# Power.net
KiCad netlist of a schematic drawn in Altium Designer
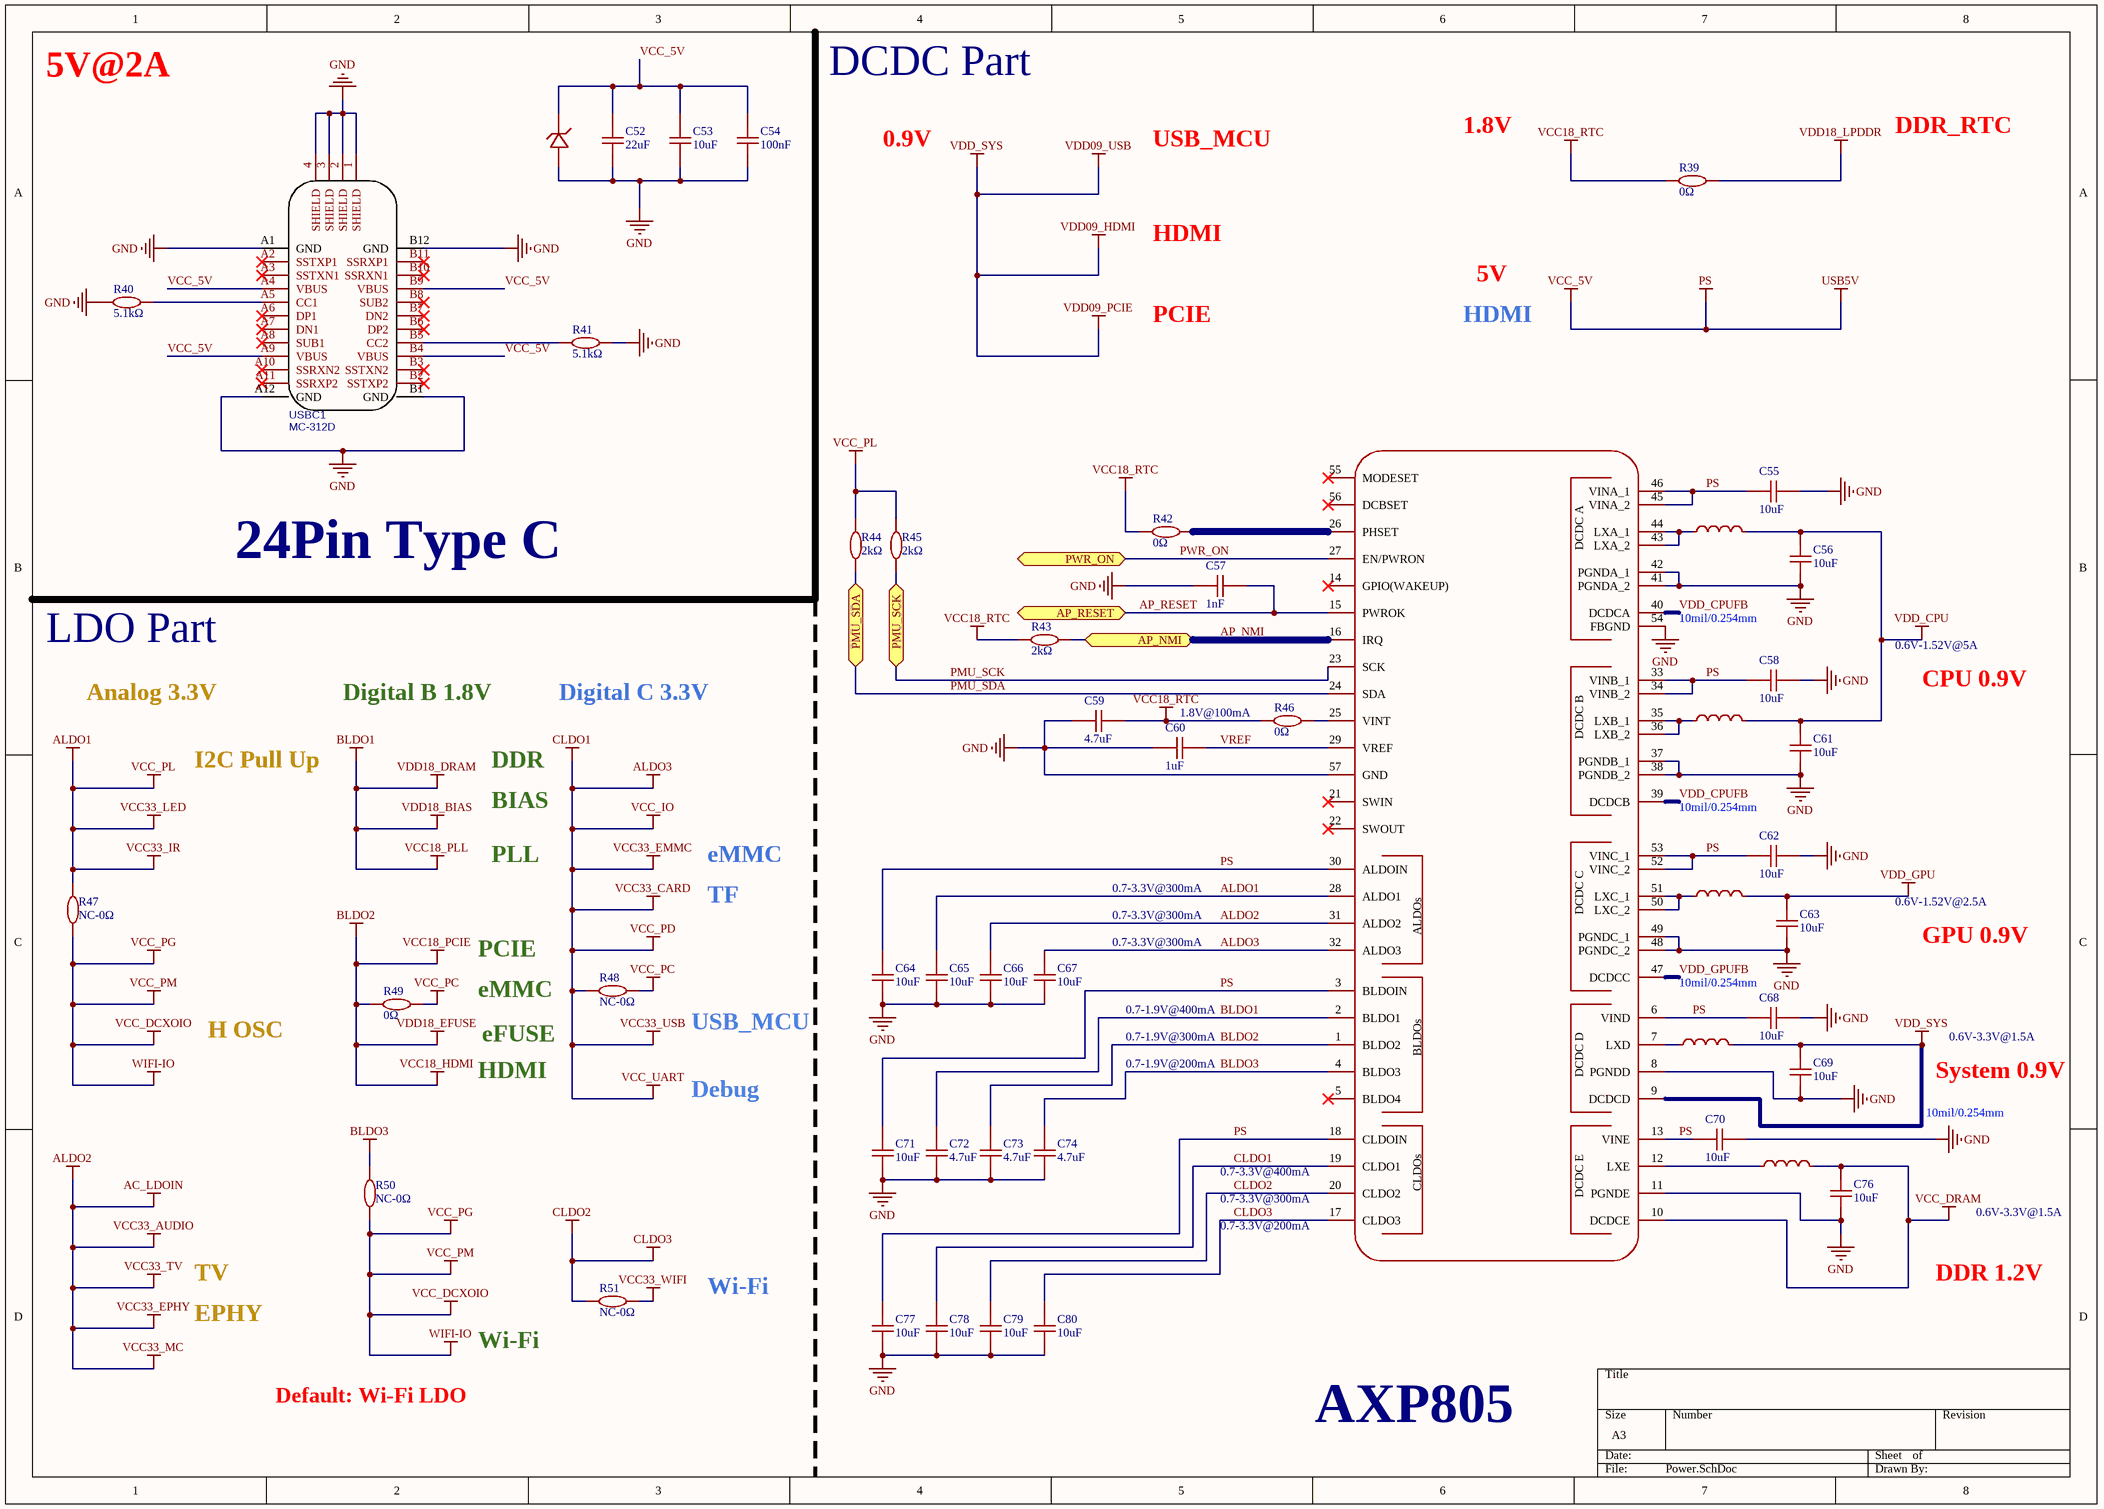
[diagram p0: Power.SchDoc]

(export (version "E")
  (design (tool "Eeschema 10.0.6"))
  (components
    (comp (ref "C52")
      (value "22uF")
      (footprint "C0603")
      (description "16V 22uF X5R ±20% 0603 Ceramic Capacitors ROHS")
      (libsource (lib "RLC") (part "22uF"))
    )
    (comp (ref "C53")
      (value "10uF")
      (footprint "C0603")
      (description "10V 10uF X5R ±10% 0603 Ceramic Capacitors ROHS")
      (libsource (lib "RLC") (part "10uF"))
    )
    (comp (ref "C54")
      (value "100nF")
      (footprint "C0402")
      (description "50V 100nF X7R ±10% 0402 Ceramic Capacitors ROHS")
      (libsource (lib "RLC") (part "100nF"))
    )
    (comp (ref "C55")
      (value "10uF")
      (footprint "C0603")
      (description "10V 10uF X5R ±10% 0603 Ceramic Capacitors ROHS")
      (libsource (lib "RLC") (part "10uF"))
    )
    (comp (ref "C56")
      (value "10uF")
      (footprint "C0603")
      (description "10V 10uF X5R ±10% 0603 Ceramic Capacitors ROHS")
      (libsource (lib "RLC") (part "10uF"))
    )
    (comp (ref "C57")
      (value "1nF")
      (footprint "C0402")
      (description "50V 1nF X7R ±10% 0402 Ceramic Capacitors ROHS")
      (libsource (lib "RLC") (part "1nF"))
    )
    (comp (ref "C58")
      (value "10uF")
      (footprint "C0603")
      (description "10V 10uF X5R ±10% 0603 Ceramic Capacitors ROHS")
      (libsource (lib "RLC") (part "10uF"))
    )
    (comp (ref "C59")
      (value "4.7uF")
      (footprint "C0402")
      (description "10V 4.7uF X5R ±20% 0402 Ceramic Capacitors ROHS")
      (libsource (lib "RLC") (part "4.7uF"))
    )
    (comp (ref "C60")
      (value "1uF")
      (footprint "C0402")
      (description "50V 1uF X5R ±10% 0402 Ceramic Capacitors ROHS")
      (libsource (lib "RLC") (part "1uF"))
    )
    (comp (ref "C61")
      (value "10uF")
      (footprint "C0603")
      (description "10V 10uF X5R ±10% 0603 Ceramic Capacitors ROHS")
      (libsource (lib "RLC") (part "10uF"))
    )
    (comp (ref "C62")
      (value "10uF")
      (footprint "C0603")
      (description "10V 10uF X5R ±10% 0603 Ceramic Capacitors ROHS")
      (libsource (lib "RLC") (part "10uF"))
    )
    (comp (ref "C63")
      (value "10uF")
      (footprint "C0603")
      (description "10V 10uF X5R ±10% 0603 Ceramic Capacitors ROHS")
      (libsource (lib "RLC") (part "10uF"))
    )
    (comp (ref "C64")
      (value "10uF")
      (footprint "C0603")
      (description "10V 10uF X5R ±10% 0603 Ceramic Capacitors ROHS")
      (libsource (lib "RLC") (part "10uF"))
    )
    (comp (ref "C65")
      (value "10uF")
      (footprint "C0603")
      (description "10V 10uF X5R ±10% 0603 Ceramic Capacitors ROHS")
      (libsource (lib "RLC") (part "10uF"))
    )
    (comp (ref "C66")
      (value "10uF")
      (footprint "C0603")
      (description "10V 10uF X5R ±10% 0603 Ceramic Capacitors ROHS")
      (libsource (lib "RLC") (part "10uF"))
    )
    (comp (ref "C67")
      (value "10uF")
      (footprint "C0603")
      (description "10V 10uF X5R ±10% 0603 Ceramic Capacitors ROHS")
      (libsource (lib "RLC") (part "10uF"))
    )
    (comp (ref "C68")
      (value "10uF")
      (footprint "C0603")
      (description "10V 10uF X5R ±10% 0603 Ceramic Capacitors ROHS")
      (libsource (lib "RLC") (part "10uF"))
    )
    (comp (ref "C69")
      (value "10uF")
      (footprint "C0603")
      (description "10V 10uF X5R ±10% 0603 Ceramic Capacitors ROHS")
      (libsource (lib "RLC") (part "10uF"))
    )
    (comp (ref "C70")
      (value "10uF")
      (footprint "C0603")
      (description "10V 10uF X5R ±10% 0603 Ceramic Capacitors ROHS")
      (libsource (lib "RLC") (part "10uF"))
    )
    (comp (ref "C71")
      (value "10uF")
      (footprint "C0603")
      (description "10V 10uF X5R ±10% 0603 Ceramic Capacitors ROHS")
      (libsource (lib "RLC") (part "10uF"))
    )
    (comp (ref "C72")
      (value "4.7uF")
      (footprint "C0402")
      (description "10V 4.7uF X5R ±20% 0402 Ceramic Capacitors ROHS")
      (libsource (lib "RLC") (part "4.7uF"))
    )
    (comp (ref "C73")
      (value "4.7uF")
      (footprint "C0402")
      (description "10V 4.7uF X5R ±20% 0402 Ceramic Capacitors ROHS")
      (libsource (lib "RLC") (part "4.7uF"))
    )
    (comp (ref "C74")
      (value "4.7uF")
      (footprint "C0402")
      (description "10V 4.7uF X5R ±20% 0402 Ceramic Capacitors ROHS")
      (libsource (lib "RLC") (part "4.7uF"))
    )
    (comp (ref "C76")
      (value "10uF")
      (footprint "C0603")
      (description "10V 10uF X5R ±10% 0603 Ceramic Capacitors ROHS")
      (libsource (lib "RLC") (part "10uF"))
    )
    (comp (ref "C77")
      (value "10uF")
      (footprint "C0603")
      (description "10V 10uF X5R ±10% 0603 Ceramic Capacitors ROHS")
      (libsource (lib "RLC") (part "10uF"))
    )
    (comp (ref "C78")
      (value "10uF")
      (footprint "C0603")
      (description "10V 10uF X5R ±10% 0603 Ceramic Capacitors ROHS")
      (libsource (lib "RLC") (part "10uF"))
    )
    (comp (ref "C79")
      (value "10uF")
      (footprint "C0603")
      (description "10V 10uF X5R ±10% 0603 Ceramic Capacitors ROHS")
      (libsource (lib "RLC") (part "10uF"))
    )
    (comp (ref "C80")
      (value "10uF")
      (footprint "C0603")
      (description "10V 10uF X5R ±10% 0603 Ceramic Capacitors ROHS")
      (libsource (lib "RLC") (part "10uF"))
    )
    (comp (ref "D5")
      (value "SMAJ5.0A")
      (footprint "SMA_L4.3-W2.6-LS5.2-RD")
      (description "43.5A 400W 9.2V 6.4V Unidirectional 5V DO-214AC(SMA) TVS Diodes ROHS")
      (fields (field (name "MANUFACTURER") "Littelfuse(美国力特)"))
      (libsource (lib "LED") (part "SMAJ5.0A_C83329"))
    )
    (comp (ref "L2")
      (value "1.5uH")
      (footprint "IND-SMD_L4.0-W4.0")
      (description "4.15A 1.5uH ±30% 18mΩ SMD,4x4mm Fixed Inductors ROHS")
      (fields
        (field (name "MANUFACTURER") "Sunltech(顺磁)")
        (field (name "MANUFACTURER PART") "SLW4030S1R0NST")
      )
      (libsource (lib "RLC") (part "SLW4030S1R5NST"))
    )
    (comp (ref "L3")
      (value "1.5uH")
      (footprint "IND-SMD_L4.0-W4.0")
      (description "4.15A 1.5uH ±30% 18mΩ SMD,4x4mm Fixed Inductors ROHS")
      (fields
        (field (name "MANUFACTURER") "Sunltech(顺磁)")
        (field (name "MANUFACTURER PART") "SLW4030S1R0NST")
      )
      (libsource (lib "RLC") (part "SLW4030S1R5NST"))
    )
    (comp (ref "L4")
      (value "1.5uH")
      (footprint "IND-SMD_L4.0-W4.0")
      (description "4.15A 1.5uH ±30% 18mΩ SMD,4x4mm Fixed Inductors ROHS")
      (fields
        (field (name "MANUFACTURER") "Sunltech(顺磁)")
        (field (name "MANUFACTURER PART") "SLW4030S1R0NST")
      )
      (libsource (lib "RLC") (part "SLW4030S1R5NST"))
    )
    (comp (ref "L5")
      (value "1.5uH")
      (footprint "IND-SMD_L4.0-W4.0")
      (description "4.15A 1.5uH ±30% 18mΩ SMD,4x4mm Fixed Inductors ROHS")
      (fields
        (field (name "MANUFACTURER") "Sunltech(顺磁)")
        (field (name "MANUFACTURER PART") "SLW4030S1R0NST")
      )
      (libsource (lib "RLC") (part "SLW4030S1R5NST"))
    )
    (comp (ref "L6")
      (value "1.5uH")
      (footprint "IND-SMD_L4.0-W4.0")
      (description "4.15A 1.5uH ±30% 18mΩ SMD,4x4mm Fixed Inductors ROHS")
      (fields
        (field (name "MANUFACTURER") "Sunltech(顺磁)")
        (field (name "MANUFACTURER PART") "SLW4030S1R0NST")
      )
      (libsource (lib "RLC") (part "SLW4030S1R5NST"))
    )
    (comp (ref "R39")
      (value "0Ω")
      (footprint "R0402")
      (description "0Ω 62.5mW 50V Thick Film Resistor ±1% 0402 Chip Resistor - Surface Mount ROHS")
      (libsource (lib "RLC") (part "0Ω"))
    )
    (comp (ref "R40")
      (value "5.1kΩ")
      (footprint "R0402")
      (description "5.1kΩ 62.5mW 50V ±100ppm/℃ Thick Film Resistor ±1% 0402 Chip Resistor - Surface Mount ROHS")
      (libsource (lib "RLC") (part "5.1kΩ"))
    )
    (comp (ref "R41")
      (value "5.1kΩ")
      (footprint "R0402")
      (description "5.1kΩ 62.5mW 50V ±100ppm/℃ Thick Film Resistor ±1% 0402 Chip Resistor - Surface Mount ROHS")
      (libsource (lib "RLC") (part "5.1kΩ"))
    )
    (comp (ref "R42")
      (value "0Ω")
      (footprint "R0402")
      (description "0Ω 62.5mW 50V Thick Film Resistor ±1% 0402 Chip Resistor - Surface Mount ROHS")
      (libsource (lib "RLC") (part "0Ω"))
    )
    (comp (ref "R43")
      (value "2kΩ")
      (footprint "R0402")
      (description "100mW 2kΩ 75V ±100ppm/℃ Thick Film Resistor ±1% 0402 Chip Resistor - Surface Mount ROHS")
      (libsource (lib "RLC") (part "2kΩ"))
    )
    (comp (ref "R44")
      (value "2kΩ")
      (footprint "R0402")
      (description "100mW 2kΩ 75V ±100ppm/℃ Thick Film Resistor ±1% 0402 Chip Resistor - Surface Mount ROHS")
      (libsource (lib "RLC") (part "2kΩ"))
    )
    (comp (ref "R45")
      (value "2kΩ")
      (footprint "R0402")
      (description "100mW 2kΩ 75V ±100ppm/℃ Thick Film Resistor ±1% 0402 Chip Resistor - Surface Mount ROHS")
      (libsource (lib "RLC") (part "2kΩ"))
    )
    (comp (ref "R46")
      (value "0Ω")
      (footprint "R0402")
      (description "0Ω 62.5mW 50V Thick Film Resistor ±1% 0402 Chip Resistor - Surface Mount ROHS")
      (libsource (lib "RLC") (part "0Ω"))
    )
    (comp (ref "R47")
      (value "NC-0Ω")
      (footprint "R0402")
      (description "0Ω 62.5mW 50V Thick Film Resistor ±1% 0402 Chip Resistor - Surface Mount ROHS")
      (libsource (lib "RLC") (part "0Ω"))
    )
    (comp (ref "R48")
      (value "NC-0Ω")
      (footprint "R0402")
      (description "0Ω 62.5mW 50V Thick Film Resistor ±1% 0402 Chip Resistor - Surface Mount ROHS")
      (libsource (lib "RLC") (part "0Ω"))
    )
    (comp (ref "R49")
      (value "0Ω")
      (footprint "R0402")
      (description "0Ω 62.5mW 50V Thick Film Resistor ±1% 0402 Chip Resistor - Surface Mount ROHS")
      (libsource (lib "RLC") (part "0Ω"))
    )
    (comp (ref "R50")
      (value "NC-0Ω")
      (footprint "R0402")
      (description "0Ω 62.5mW 50V Thick Film Resistor ±1% 0402 Chip Resistor - Surface Mount ROHS")
      (libsource (lib "RLC") (part "0Ω"))
    )
    (comp (ref "R51")
      (value "NC-0Ω")
      (footprint "R0402")
      (description "0Ω 62.5mW 50V Thick Film Resistor ±1% 0402 Chip Resistor - Surface Mount ROHS")
      (libsource (lib "RLC") (part "0Ω"))
    )
    (comp (ref "U4")
      (value "AXP805")
      (footprint "QFN-56_L7.0-W7.0-P0.40-TL-EP4.6")
      (libsource (lib "IC") (part "AXP805"))
    )
    (comp (ref "USBC1")
      (value "MC-312D")
      (footprint "USB-C-SMD_MC-312D-C")
      (description "1 24P Type-C SMD USB, DVI, HDMI Connector Assemblies ROHS")
      (fields
        (field (name "MANUFACTURER") "SOFNG(硕方)")
        (field (name "MANUFACTURER PART") "MC-312D-C")
        (field (name "CONTRIBUTOR") "LCSC")
      )
      (libsource (lib "Connector") (part "MC-312D"))
    )
  )
  (nets
    (net (code "1") (name "/AP_NMI") (class "Default")
      (node (ref "R43") (pin "2") (pinfunction "2_2") (pintype "passive"))
      (node (ref "U4") (pin "16") (pinfunction "IRQ_16") (pintype "passive"))
    )
    (net (code "2") (name "/AP_RESET") (class "Default")
      (node (ref "C57") (pin "2") (pinfunction "2_2") (pintype "passive"))
      (node (ref "U4") (pin "15") (pinfunction "PWROK_15") (pintype "passive"))
    )
    (net (code "3") (name "/PMU_SCK") (class "Default")
      (node (ref "R45") (pin "1") (pinfunction "1_1") (pintype "passive"))
      (node (ref "U4") (pin "23") (pinfunction "SCK_23") (pintype "passive"))
    )
    (net (code "4") (name "/PMU_SDA") (class "Default")
      (node (ref "R44") (pin "1") (pinfunction "1_1") (pintype "passive"))
      (node (ref "U4") (pin "24") (pinfunction "SDA_24") (pintype "passive"))
    )
    (net (code "5") (name "/PWR_ON") (class "Default")
      (node (ref "U4") (pin "27") (pinfunction "EN/PWRON_27") (pintype "passive"))
    )
    (net (code "6") (name "/VDD_CPUFB") (class "Default")
      (node (ref "U4") (pin "39") (pinfunction "DCDCB_39") (pintype "passive"))
      (node (ref "U4") (pin "40") (pinfunction "DCDCA_40") (pintype "passive"))
    )
    (net (code "7") (name "/VDD_GPUFB") (class "Default")
      (node (ref "U4") (pin "47") (pinfunction "DCDCC_47") (pintype "passive"))
    )
    (net (code "8") (name "/VREF") (class "Default")
      (node (ref "C60") (pin "2") (pinfunction "2_2") (pintype "passive"))
      (node (ref "U4") (pin "29") (pinfunction "VREF_29") (pintype "passive"))
    )
    (net (code "9") (name "AC_LDOIN") (class "Default")
      (node (ref "C66") (pin "2") (pinfunction "2_2") (pintype "passive"))
      (node (ref "U4") (pin "31") (pinfunction "ALDO2_31") (pintype "passive"))
    )
    (net (code "10") (name "ALDO1") (class "Default")
      (node (ref "C65") (pin "2") (pinfunction "2_2") (pintype "passive"))
      (node (ref "R44") (pin "2") (pinfunction "2_2") (pintype "passive"))
      (node (ref "R45") (pin "2") (pinfunction "2_2") (pintype "passive"))
      (node (ref "R47") (pin "2") (pinfunction "2_2") (pintype "passive"))
      (node (ref "U4") (pin "28") (pinfunction "ALDO1_28") (pintype "passive"))
    )
    (net (code "11") (name "ALDO3") (class "Default")
      (node (ref "C67") (pin "2") (pinfunction "2_2") (pintype "passive"))
      (node (ref "C78") (pin "2") (pinfunction "2_2") (pintype "passive"))
      (node (ref "R48") (pin "2") (pinfunction "2_2") (pintype "passive"))
      (node (ref "U4") (pin "19") (pinfunction "CLDO1_19") (pintype "passive"))
      (node (ref "U4") (pin "32") (pinfunction "ALDO3_32") (pintype "passive"))
    )
    (net (code "12") (name "BLDO1") (class "Default")
      (node (ref "C72") (pin "2") (pinfunction "2_2") (pintype "passive"))
      (node (ref "U4") (pin "2") (pinfunction "BLDO1_2") (pintype "passive"))
    )
    (net (code "13") (name "BLDO2") (class "Default")
      (node (ref "C73") (pin "2") (pinfunction "2_2") (pintype "passive"))
      (node (ref "R49") (pin "1") (pinfunction "1_1") (pintype "passive"))
      (node (ref "U4") (pin "1") (pinfunction "BLDO2_1") (pintype "passive"))
    )
    (net (code "14") (name "BLDO3") (class "Default")
      (node (ref "C74") (pin "2") (pinfunction "2_2") (pintype "passive"))
      (node (ref "R50") (pin "2") (pinfunction "2_2") (pintype "passive"))
      (node (ref "U4") (pin "4") (pinfunction "BLDO3_4") (pintype "passive"))
    )
    (net (code "15") (name "CLDO2") (class "Default")
      (node (ref "C79") (pin "2") (pinfunction "2_2") (pintype "passive"))
      (node (ref "C80") (pin "2") (pinfunction "2_2") (pintype "passive"))
      (node (ref "R51") (pin "2") (pinfunction "2_2") (pintype "passive"))
      (node (ref "U4") (pin "17") (pinfunction "CLDO3_17") (pintype "passive"))
      (node (ref "U4") (pin "20") (pinfunction "CLDO2_20") (pintype "passive"))
    )
    (net (code "16") (name "GND") (class "Default")
      (node (ref "C52") (pin "1") (pinfunction "1_1") (pintype "passive"))
      (node (ref "C53") (pin "1") (pinfunction "1_1") (pintype "passive"))
      (node (ref "C54") (pin "1") (pinfunction "1_1") (pintype "passive"))
      (node (ref "C55") (pin "1") (pinfunction "1_1") (pintype "passive"))
      (node (ref "C56") (pin "1") (pinfunction "1_1") (pintype "passive"))
      (node (ref "C57") (pin "1") (pinfunction "1_1") (pintype "passive"))
      (node (ref "C58") (pin "1") (pinfunction "1_1") (pintype "passive"))
      (node (ref "C59") (pin "1") (pinfunction "1_1") (pintype "passive"))
      (node (ref "C60") (pin "1") (pinfunction "1_1") (pintype "passive"))
      (node (ref "C61") (pin "1") (pinfunction "1_1") (pintype "passive"))
      (node (ref "C62") (pin "1") (pinfunction "1_1") (pintype "passive"))
      (node (ref "C63") (pin "1") (pinfunction "1_1") (pintype "passive"))
      (node (ref "C64") (pin "1") (pinfunction "1_1") (pintype "passive"))
      (node (ref "C65") (pin "1") (pinfunction "1_1") (pintype "passive"))
      (node (ref "C66") (pin "1") (pinfunction "1_1") (pintype "passive"))
      (node (ref "C67") (pin "1") (pinfunction "1_1") (pintype "passive"))
      (node (ref "C68") (pin "1") (pinfunction "1_1") (pintype "passive"))
      (node (ref "C69") (pin "1") (pinfunction "1_1") (pintype "passive"))
      (node (ref "C70") (pin "1") (pinfunction "1_1") (pintype "passive"))
      (node (ref "C71") (pin "1") (pinfunction "1_1") (pintype "passive"))
      (node (ref "C72") (pin "1") (pinfunction "1_1") (pintype "passive"))
      (node (ref "C73") (pin "1") (pinfunction "1_1") (pintype "passive"))
      (node (ref "C74") (pin "1") (pinfunction "1_1") (pintype "passive"))
      (node (ref "C76") (pin "1") (pinfunction "1_1") (pintype "passive"))
      (node (ref "C77") (pin "1") (pinfunction "1_1") (pintype "passive"))
      (node (ref "C78") (pin "1") (pinfunction "1_1") (pintype "passive"))
      (node (ref "C79") (pin "1") (pinfunction "1_1") (pintype "passive"))
      (node (ref "C80") (pin "1") (pinfunction "1_1") (pintype "passive"))
      (node (ref "D5") (pin "2") (pinfunction "A_2") (pintype "passive"))
      (node (ref "R40") (pin "1") (pinfunction "1_1") (pintype "passive"))
      (node (ref "R41") (pin "2") (pinfunction "2_2") (pintype "passive"))
      (node (ref "U4") (pin "11") (pinfunction "PGNDE_11") (pintype "passive"))
      (node (ref "U4") (pin "37") (pinfunction "PGNDB_1_37") (pintype "passive"))
      (node (ref "U4") (pin "38") (pinfunction "PGNDB_2_38") (pintype "passive"))
      (node (ref "U4") (pin "41") (pinfunction "PGNDA_2_41") (pintype "passive"))
      (node (ref "U4") (pin "42") (pinfunction "PGNDA_1_42") (pintype "passive"))
      (node (ref "U4") (pin "48") (pinfunction "PGNDC_2_48") (pintype "passive"))
      (node (ref "U4") (pin "49") (pinfunction "PGNDC_1_49") (pintype "passive"))
      (node (ref "U4") (pin "54") (pinfunction "FBGND_54") (pintype "passive"))
      (node (ref "U4") (pin "57") (pinfunction "GND_57") (pintype "passive"))
      (node (ref "U4") (pin "8") (pinfunction "PGNDD_8") (pintype "passive"))
      (node (ref "USBC1") (pin "1") (pinfunction "SHIELD_1") (pintype "passive"))
      (node (ref "USBC1") (pin "2") (pinfunction "SHIELD_2") (pintype "passive"))
      (node (ref "USBC1") (pin "3") (pinfunction "SHIELD_3") (pintype "passive"))
      (node (ref "USBC1") (pin "4") (pinfunction "SHIELD_4") (pintype "passive"))
      (node (ref "USBC1") (pin "A1") (pinfunction "GND_A1") (pintype "passive"))
      (node (ref "USBC1") (pin "A12") (pinfunction "GND_A12") (pintype "passive"))
      (node (ref "USBC1") (pin "B1") (pinfunction "GND_B1") (pintype "passive"))
      (node (ref "USBC1") (pin "B12") (pinfunction "GND_B12") (pintype "passive"))
    )
    (net (code "17") (name "Net-(U4-LXA_1)") (class "Default")
      (node (ref "L2") (pin "1") (pinfunction "1_1") (pintype "passive"))
      (node (ref "U4") (pin "43") (pinfunction "LXA_2_43") (pintype "passive"))
      (node (ref "U4") (pin "44") (pinfunction "LXA_1_44") (pintype "passive"))
    )
    (net (code "18") (name "Net-(U4-LXB_1)") (class "Default")
      (node (ref "L3") (pin "1") (pinfunction "1_1") (pintype "passive"))
      (node (ref "U4") (pin "35") (pinfunction "LXB_1_35") (pintype "passive"))
      (node (ref "U4") (pin "36") (pinfunction "LXB_2_36") (pintype "passive"))
    )
    (net (code "19") (name "Net-(U4-LXC_1)") (class "Default")
      (node (ref "L4") (pin "1") (pinfunction "1_1") (pintype "passive"))
      (node (ref "U4") (pin "50") (pinfunction "LXC_2_50") (pintype "passive"))
      (node (ref "U4") (pin "51") (pinfunction "LXC_1_51") (pintype "passive"))
    )
    (net (code "20") (name "Net-(U4-LXD)") (class "Default")
      (node (ref "L5") (pin "1") (pinfunction "1_1") (pintype "passive"))
      (node (ref "U4") (pin "7") (pinfunction "LXD_7") (pintype "passive"))
    )
    (net (code "21") (name "Net-(U4-LXE)") (class "Default")
      (node (ref "L6") (pin "1") (pinfunction "1_1") (pintype "passive"))
      (node (ref "U4") (pin "12") (pinfunction "LXE_12") (pintype "passive"))
    )
    (net (code "22") (name "Net-(U4-PHSET)") (class "Default")
      (node (ref "R42") (pin "2") (pinfunction "2_2") (pintype "passive"))
      (node (ref "U4") (pin "26") (pinfunction "PHSET_26") (pintype "passive"))
    )
    (net (code "23") (name "Net-(U4-VINT)") (class "Default")
      (node (ref "R46") (pin "2") (pinfunction "2_2") (pintype "passive"))
      (node (ref "U4") (pin "25") (pinfunction "VINT_25") (pintype "passive"))
    )
    (net (code "24") (name "Net-(USBC1-CC1)") (class "Default")
      (node (ref "R40") (pin "2") (pinfunction "2_2") (pintype "passive"))
      (node (ref "USBC1") (pin "A5") (pinfunction "CC1_A5") (pintype "passive"))
    )
    (net (code "25") (name "Net-(USBC1-CC2)") (class "Default")
      (node (ref "R41") (pin "1") (pinfunction "1_1") (pintype "passive"))
      (node (ref "USBC1") (pin "B5") (pinfunction "CC2_B5") (pintype "passive"))
    )
    (net (code "26") (name "PS") (class "Default")
      (node (ref "C52") (pin "2") (pinfunction "2_2") (pintype "passive"))
      (node (ref "C53") (pin "2") (pinfunction "2_2") (pintype "passive"))
      (node (ref "C54") (pin "2") (pinfunction "2_2") (pintype "passive"))
      (node (ref "C55") (pin "2") (pinfunction "2_2") (pintype "passive"))
      (node (ref "C58") (pin "2") (pinfunction "2_2") (pintype "passive"))
      (node (ref "C62") (pin "2") (pinfunction "2_2") (pintype "passive"))
      (node (ref "C64") (pin "2") (pinfunction "2_2") (pintype "passive"))
      (node (ref "C68") (pin "2") (pinfunction "2_2") (pintype "passive"))
      (node (ref "C70") (pin "2") (pinfunction "2_2") (pintype "passive"))
      (node (ref "C71") (pin "2") (pinfunction "2_2") (pintype "passive"))
      (node (ref "C77") (pin "2") (pinfunction "2_2") (pintype "passive"))
      (node (ref "D5") (pin "1") (pinfunction "C_1") (pintype "passive"))
      (node (ref "U4") (pin "13") (pinfunction "VINE_13") (pintype "passive"))
      (node (ref "U4") (pin "18") (pinfunction "CLDOIN_18") (pintype "passive"))
      (node (ref "U4") (pin "3") (pinfunction "BLDOIN_3") (pintype "passive"))
      (node (ref "U4") (pin "30") (pinfunction "ALDOIN_30") (pintype "passive"))
      (node (ref "U4") (pin "33") (pinfunction "VINB_1_33") (pintype "passive"))
      (node (ref "U4") (pin "34") (pinfunction "VINB_2_34") (pintype "passive"))
      (node (ref "U4") (pin "45") (pinfunction "VINA_2_45") (pintype "passive"))
      (node (ref "U4") (pin "46") (pinfunction "VINA_1_46") (pintype "passive"))
      (node (ref "U4") (pin "52") (pinfunction "VINC_2_52") (pintype "passive"))
      (node (ref "U4") (pin "53") (pinfunction "VINC_1_53") (pintype "passive"))
      (node (ref "U4") (pin "6") (pinfunction "VIND_6") (pintype "passive"))
      (node (ref "USBC1") (pin "A4") (pinfunction "VBUS_A4") (pintype "passive"))
      (node (ref "USBC1") (pin "A9") (pinfunction "VBUS_A9") (pintype "passive"))
      (node (ref "USBC1") (pin "B4") (pinfunction "VBUS_B4") (pintype "passive"))
      (node (ref "USBC1") (pin "B9") (pinfunction "VBUS_B9") (pintype "passive"))
    )
    (net (code "27") (name "VCC18_RTC") (class "Default")
      (node (ref "C59") (pin "2") (pinfunction "2_2") (pintype "passive"))
      (node (ref "R39") (pin "1") (pinfunction "1_1") (pintype "passive"))
      (node (ref "R42") (pin "1") (pinfunction "1_1") (pintype "passive"))
      (node (ref "R43") (pin "1") (pinfunction "1_1") (pintype "passive"))
      (node (ref "R46") (pin "1") (pinfunction "1_1") (pintype "passive"))
    )
    (net (code "28") (name "VCC33_WIFI") (class "Default")
      (node (ref "R51") (pin "1") (pinfunction "1_1") (pintype "passive"))
    )
    (net (code "29") (name "VCC_DCXOIO") (class "Default")
      (node (ref "R47") (pin "1") (pinfunction "1_1") (pintype "passive"))
      (node (ref "R50") (pin "1") (pinfunction "1_1") (pintype "passive"))
    )
    (net (code "30") (name "VCC_DRAM") (class "Default")
      (node (ref "C76") (pin "2") (pinfunction "2_2") (pintype "passive"))
      (node (ref "L6") (pin "2") (pinfunction "2_2") (pintype "passive"))
      (node (ref "U4") (pin "10") (pinfunction "DCDCE_10") (pintype "passive"))
    )
    (net (code "31") (name "VCC_PC") (class "Default")
      (node (ref "R48") (pin "1") (pinfunction "1_1") (pintype "passive"))
      (node (ref "R49") (pin "2") (pinfunction "2_2") (pintype "passive"))
    )
    (net (code "32") (name "VDD09_HDMI") (class "Default")
      (node (ref "C69") (pin "2") (pinfunction "2_2") (pintype "passive"))
      (node (ref "L5") (pin "2") (pinfunction "2_2") (pintype "passive"))
      (node (ref "U4") (pin "9") (pinfunction "DCDCD_9") (pintype "passive"))
    )
    (net (code "33") (name "VDD18_LPDDR") (class "Default")
      (node (ref "R39") (pin "2") (pinfunction "2_2") (pintype "passive"))
    )
    (net (code "34") (name "VDD_CPU") (class "Default")
      (node (ref "C56") (pin "2") (pinfunction "2_2") (pintype "passive"))
      (node (ref "C61") (pin "2") (pinfunction "2_2") (pintype "passive"))
      (node (ref "L2") (pin "2") (pinfunction "2_2") (pintype "passive"))
      (node (ref "L3") (pin "2") (pinfunction "2_2") (pintype "passive"))
    )
    (net (code "35") (name "VDD_GPU") (class "Default")
      (node (ref "C63") (pin "2") (pinfunction "2_2") (pintype "passive"))
      (node (ref "L4") (pin "2") (pinfunction "2_2") (pintype "passive"))
    )
    (net (code "36") (name "unconnected-(U4-BLDO4-Pad5)") (class "Default")
      (node (ref "U4") (pin "5") (pinfunction "BLDO4_5") (pintype "passive+no_connect"))
    )
    (net (code "37") (name "unconnected-(U4-DCBSET-Pad56)") (class "Default")
      (node (ref "U4") (pin "56") (pinfunction "DCBSET_56") (pintype "passive+no_connect"))
    )
    (net (code "38") (name "unconnected-(U4-GPIO(WAKEUP)-Pad14)") (class "Default")
      (node (ref "U4") (pin "14") (pinfunction "GPIO(WAKEUP)_14") (pintype "passive+no_connect"))
    )
    (net (code "39") (name "unconnected-(U4-MODESET-Pad55)") (class "Default")
      (node (ref "U4") (pin "55") (pinfunction "MODESET_55") (pintype "passive+no_connect"))
    )
    (net (code "40") (name "unconnected-(U4-SWIN-Pad21)") (class "Default")
      (node (ref "U4") (pin "21") (pinfunction "SWIN_21") (pintype "passive+no_connect"))
    )
    (net (code "41") (name "unconnected-(U4-SWOUT-Pad22)") (class "Default")
      (node (ref "U4") (pin "22") (pinfunction "SWOUT_22") (pintype "passive+no_connect"))
    )
    (net (code "42") (name "unconnected-(USBC1-DN1-PadA7)") (class "Default")
      (node (ref "USBC1") (pin "A7") (pinfunction "DN1_A7") (pintype "passive+no_connect"))
    )
    (net (code "43") (name "unconnected-(USBC1-DN2-PadB7)") (class "Default")
      (node (ref "USBC1") (pin "B7") (pinfunction "DN2_B7") (pintype "passive+no_connect"))
    )
    (net (code "44") (name "unconnected-(USBC1-DP1-PadA6)") (class "Default")
      (node (ref "USBC1") (pin "A6") (pinfunction "DP1_A6") (pintype "passive+no_connect"))
    )
    (net (code "45") (name "unconnected-(USBC1-DP2-PadB6)") (class "Default")
      (node (ref "USBC1") (pin "B6") (pinfunction "DP2_B6") (pintype "passive+no_connect"))
    )
    (net (code "46") (name "unconnected-(USBC1-SSRXN1-PadB10)") (class "Default")
      (node (ref "USBC1") (pin "B10") (pinfunction "SSRXN1_B10") (pintype "passive+no_connect"))
    )
    (net (code "47") (name "unconnected-(USBC1-SSRXN2-PadA10)") (class "Default")
      (node (ref "USBC1") (pin "A10") (pinfunction "SSRXN2_A10") (pintype "passive+no_connect"))
    )
    (net (code "48") (name "unconnected-(USBC1-SSRXP1-PadB11)") (class "Default")
      (node (ref "USBC1") (pin "B11") (pinfunction "SSRXP1_B11") (pintype "passive+no_connect"))
    )
    (net (code "49") (name "unconnected-(USBC1-SSRXP2-PadA11)") (class "Default")
      (node (ref "USBC1") (pin "A11") (pinfunction "SSRXP2_A11") (pintype "passive+no_connect"))
    )
    (net (code "50") (name "unconnected-(USBC1-SSTXN1-PadA3)") (class "Default")
      (node (ref "USBC1") (pin "A3") (pinfunction "SSTXN1_A3") (pintype "passive+no_connect"))
    )
    (net (code "51") (name "unconnected-(USBC1-SSTXN2-PadB3)") (class "Default")
      (node (ref "USBC1") (pin "B3") (pinfunction "SSTXN2_B3") (pintype "passive+no_connect"))
    )
    (net (code "52") (name "unconnected-(USBC1-SSTXP1-PadA2)") (class "Default")
      (node (ref "USBC1") (pin "A2") (pinfunction "SSTXP1_A2") (pintype "passive+no_connect"))
    )
    (net (code "53") (name "unconnected-(USBC1-SSTXP2-PadB2)") (class "Default")
      (node (ref "USBC1") (pin "B2") (pinfunction "SSTXP2_B2") (pintype "passive+no_connect"))
    )
    (net (code "54") (name "unconnected-(USBC1-SUB1-PadA8)") (class "Default")
      (node (ref "USBC1") (pin "A8") (pinfunction "SUB1_A8") (pintype "passive+no_connect"))
    )
    (net (code "55") (name "unconnected-(USBC1-SUB2-PadB8)") (class "Default")
      (node (ref "USBC1") (pin "B8") (pinfunction "SUB2_B8") (pintype "passive+no_connect"))
    )
  )
)
